# source_eagle.net
KiCad netlist of a schematic drawn in EAGLE
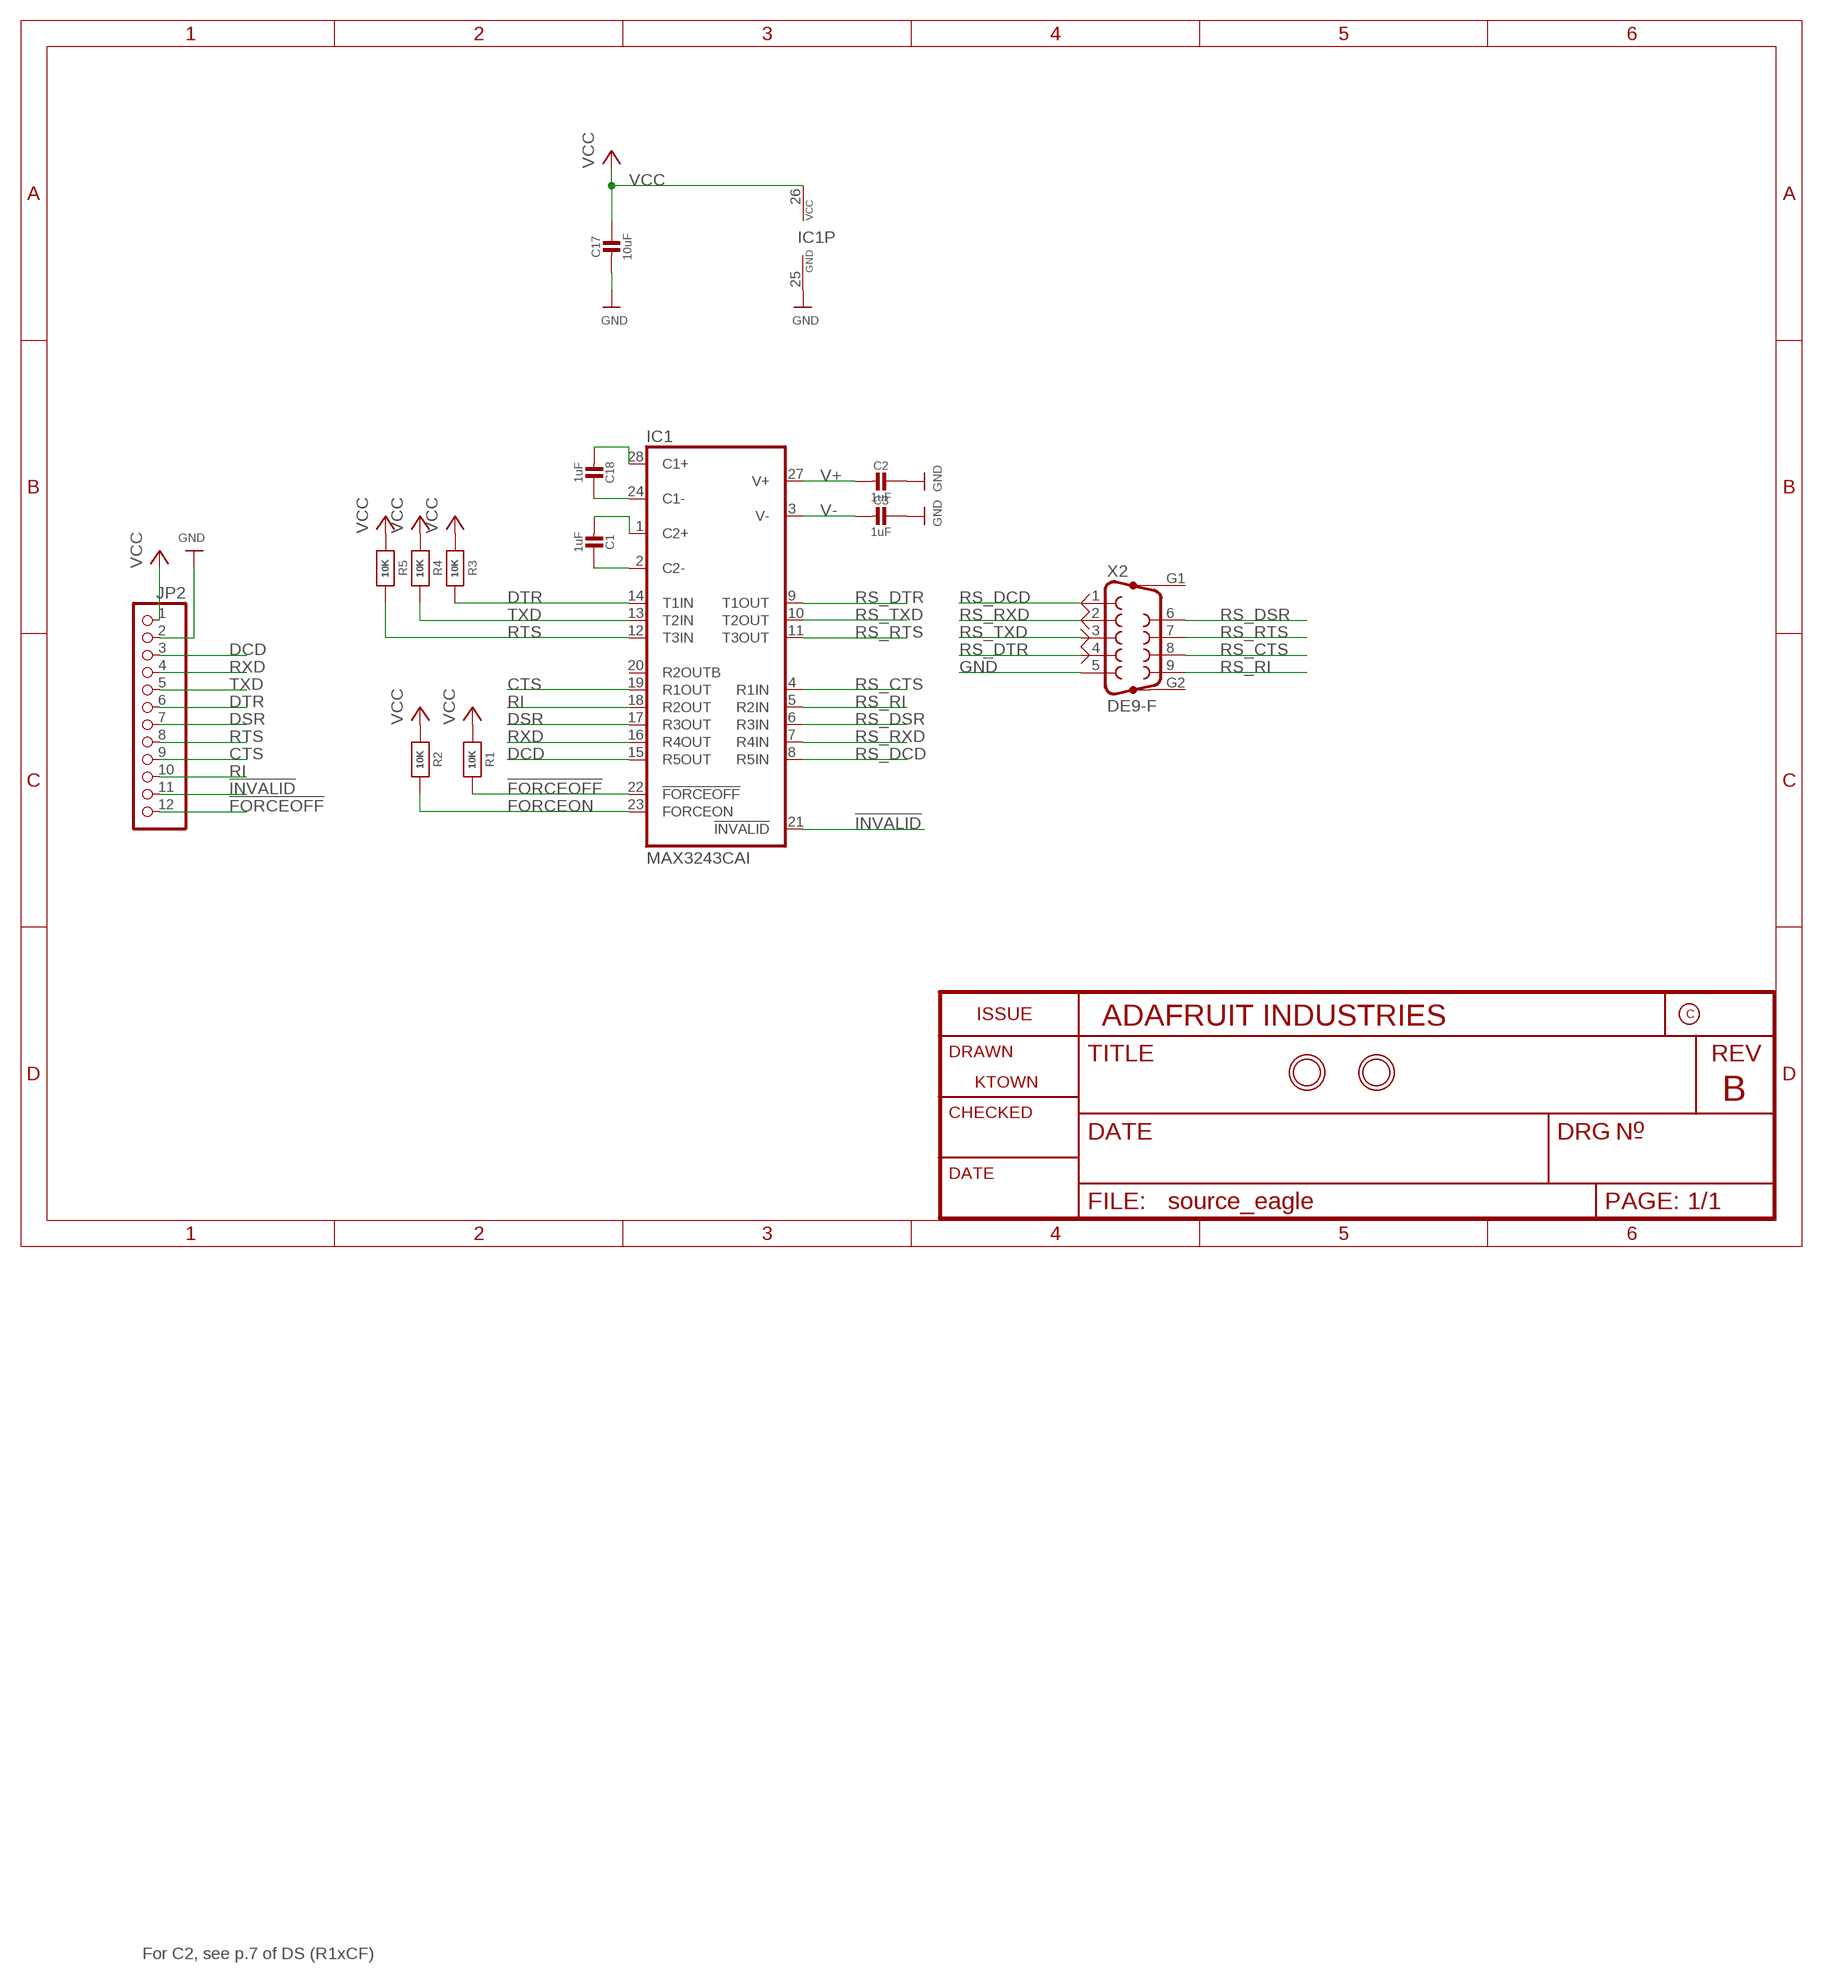
[diagram p0: schematic, sheet 1]

(export (version "E")
  (design (tool "Eeschema 10.0.6"))
  (components
    (comp (ref "C1")
      (value "1uF")
      (footprint "eagle-import:0603-NO")
      (libsource (lib "eagle-import") (part "CAP_CERAMIC0603_NO"))
    )
    (comp (ref "C2")
      (value "1uF")
      (footprint "eagle-import:0603-NO")
      (libsource (lib "eagle-import") (part "CAP_CERAMIC0603_NO"))
    )
    (comp (ref "C3")
      (value "1uF")
      (footprint "eagle-import:0603-NO")
      (libsource (lib "eagle-import") (part "CAP_CERAMIC0603_NO"))
    )
    (comp (ref "C17")
      (value "10uF")
      (footprint "eagle-import:0805-NO")
      (libsource (lib "eagle-import") (part "CAP_CERAMIC0805-NOOUTLINE"))
    )
    (comp (ref "C18")
      (value "1uF")
      (footprint "eagle-import:0603-NO")
      (libsource (lib "eagle-import") (part "CAP_CERAMIC0603_NO"))
    )
    (comp (ref "IC1")
      (value "MAX3243CAI")
      (footprint "eagle-import:SSOP28")
      (fields (field (name "MF") "MAXIM") (field (name "MPN") "MAX3243CAI+"))
      (libsource (lib "eagle-import") (part "MAX3243AIC"))
    )
    (comp (ref "JP2")
      (value "HEADER-1X1276MIL")
      (footprint "eagle-import:1X12_ROUND_76MIL")
      (libsource (lib "eagle-import") (part "HEADER-1X1276MIL"))
    )
    (comp (ref "R1")
      (value "10K")
      (footprint "eagle-import:0603-NO")
      (libsource (lib "eagle-import") (part "RESISTOR_0603_NOOUT"))
    )
    (comp (ref "R2")
      (value "10K")
      (footprint "eagle-import:0603-NO")
      (libsource (lib "eagle-import") (part "RESISTOR_0603_NOOUT"))
    )
    (comp (ref "R3")
      (value "10K")
      (footprint "eagle-import:0603-NO")
      (libsource (lib "eagle-import") (part "RESISTOR_0603_NOOUT"))
    )
    (comp (ref "R4")
      (value "10K")
      (footprint "eagle-import:0603-NO")
      (libsource (lib "eagle-import") (part "RESISTOR_0603_NOOUT"))
    )
    (comp (ref "R5")
      (value "10K")
      (footprint "eagle-import:0603-NO")
      (libsource (lib "eagle-import") (part "RESISTOR_0603_NOOUT"))
    )
    (comp (ref "U$2")
      (value "MOUNTINGHOLE3.0THIN")
      (footprint "eagle-import:MOUNTINGHOLE_3.0_PLATEDTHIN")
      (libsource (lib "eagle-import") (part "MOUNTINGHOLE3.0THIN"))
    )
    (comp (ref "U$3")
      (value "MOUNTINGHOLE3.0THIN")
      (footprint "eagle-import:MOUNTINGHOLE_3.0_PLATEDTHIN")
      (libsource (lib "eagle-import") (part "MOUNTINGHOLE3.0THIN"))
    )
    (comp (ref "X2")
      (value "DE9-F")
      (footprint "eagle-import:F09HP")
      (libsource (lib "eagle-import") (part "F09HP"))
    )
  )
  (nets
    (net (code "1") (name "/CTS") (class "Default")
      (node (ref "IC1") (pin "19") (pinfunction "R1OUT_19") (pintype "output"))
      (node (ref "JP2") (pin "9") (pinfunction "9_9") (pintype "passive"))
    )
    (net (code "2") (name "/DCD") (class "Default")
      (node (ref "IC1") (pin "15") (pinfunction "R5OUT_15") (pintype "output"))
      (node (ref "JP2") (pin "3") (pinfunction "3_3") (pintype "passive"))
    )
    (net (code "3") (name "/DSR") (class "Default")
      (node (ref "IC1") (pin "17") (pinfunction "R3OUT_17") (pintype "output"))
      (node (ref "JP2") (pin "7") (pinfunction "7_7") (pintype "passive"))
    )
    (net (code "4") (name "/DTR") (class "Default")
      (node (ref "IC1") (pin "14") (pinfunction "T1IN_14") (pintype "input"))
      (node (ref "JP2") (pin "6") (pinfunction "6_6") (pintype "passive"))
      (node (ref "R3") (pin "2") (pinfunction "2_2") (pintype "passive"))
    )
    (net (code "5") (name "/FORCEON") (class "Default")
      (node (ref "IC1") (pin "23") (pinfunction "FORCEON_23") (pintype "input"))
      (node (ref "R2") (pin "2") (pinfunction "2_2") (pintype "passive"))
    )
    (net (code "6") (name "/RI") (class "Default")
      (node (ref "IC1") (pin "18") (pinfunction "R2OUT_18") (pintype "output"))
      (node (ref "JP2") (pin "10") (pinfunction "10_10") (pintype "passive"))
    )
    (net (code "7") (name "/RS_CTS") (class "Default")
      (node (ref "IC1") (pin "4") (pinfunction "R1IN_4") (pintype "input"))
      (node (ref "X2") (pin "8") (pinfunction "8_8") (pintype "passive"))
    )
    (net (code "8") (name "/RS_DCD") (class "Default")
      (node (ref "IC1") (pin "8") (pinfunction "R5IN_8") (pintype "input"))
      (node (ref "X2") (pin "1") (pinfunction "1_1") (pintype "passive"))
    )
    (net (code "9") (name "/RS_DSR") (class "Default")
      (node (ref "IC1") (pin "6") (pinfunction "R3IN_6") (pintype "input"))
      (node (ref "X2") (pin "6") (pinfunction "6_6") (pintype "passive"))
    )
    (net (code "10") (name "/RS_DTR") (class "Default")
      (node (ref "IC1") (pin "9") (pinfunction "T1OUT_9") (pintype "output"))
      (node (ref "X2") (pin "4") (pinfunction "4_4") (pintype "passive"))
    )
    (net (code "11") (name "/RS_RI") (class "Default")
      (node (ref "IC1") (pin "5") (pinfunction "R2IN_5") (pintype "input"))
      (node (ref "X2") (pin "9") (pinfunction "9_9") (pintype "passive"))
    )
    (net (code "12") (name "/RS_RTS") (class "Default")
      (node (ref "IC1") (pin "11") (pinfunction "T3OUT_11") (pintype "output"))
      (node (ref "X2") (pin "7") (pinfunction "7_7") (pintype "passive"))
    )
    (net (code "13") (name "/RS_RXD") (class "Default")
      (node (ref "IC1") (pin "7") (pinfunction "R4IN_7") (pintype "input"))
      (node (ref "X2") (pin "2") (pinfunction "2_2") (pintype "passive"))
    )
    (net (code "14") (name "/RS_TXD") (class "Default")
      (node (ref "IC1") (pin "10") (pinfunction "T2OUT_10") (pintype "output"))
      (node (ref "X2") (pin "3") (pinfunction "3_3") (pintype "passive"))
    )
    (net (code "15") (name "/RTS") (class "Default")
      (node (ref "IC1") (pin "12") (pinfunction "T3IN_12") (pintype "input"))
      (node (ref "JP2") (pin "8") (pinfunction "8_8") (pintype "passive"))
      (node (ref "R5") (pin "2") (pinfunction "2_2") (pintype "passive"))
    )
    (net (code "16") (name "/RXD") (class "Default")
      (node (ref "IC1") (pin "16") (pinfunction "R4OUT_16") (pintype "output"))
      (node (ref "JP2") (pin "4") (pinfunction "4_4") (pintype "passive"))
    )
    (net (code "17") (name "/TXD") (class "Default")
      (node (ref "IC1") (pin "13") (pinfunction "T2IN_13") (pintype "input"))
      (node (ref "JP2") (pin "5") (pinfunction "5_5") (pintype "passive"))
      (node (ref "R4") (pin "2") (pinfunction "2_2") (pintype "passive"))
    )
    (net (code "18") (name "/V+") (class "Default")
      (node (ref "C2") (pin "2") (pinfunction "2_2") (pintype "passive"))
      (node (ref "IC1") (pin "27") (pinfunction "V+_27") (pintype "passive"))
    )
    (net (code "19") (name "/V-") (class "Default")
      (node (ref "C3") (pin "2") (pinfunction "2_2") (pintype "passive"))
      (node (ref "IC1") (pin "3") (pinfunction "V-_3") (pintype "passive"))
    )
    (net (code "20") (name "/~{FORCEOFF}") (class "Default")
      (node (ref "IC1") (pin "22") (pinfunction "~{FORCEOFF}_22") (pintype "input"))
      (node (ref "JP2") (pin "12") (pinfunction "12_12") (pintype "passive"))
      (node (ref "R1") (pin "2") (pinfunction "2_2") (pintype "passive"))
    )
    (net (code "21") (name "/~{INVALID}") (class "Default")
      (node (ref "IC1") (pin "21") (pinfunction "~{INVALID}_21") (pintype "input"))
      (node (ref "JP2") (pin "11") (pinfunction "11_11") (pintype "passive"))
    )
    (net (code "22") (name "GND") (class "Default")
      (node (ref "C17") (pin "2") (pinfunction "2_2") (pintype "passive"))
      (node (ref "C2") (pin "1") (pinfunction "1_1") (pintype "passive"))
      (node (ref "C3") (pin "1") (pinfunction "1_1") (pintype "passive"))
      (node (ref "IC1") (pin "25") (pinfunction "GND_25") (pintype "power_in"))
      (node (ref "JP2") (pin "2") (pinfunction "2_2") (pintype "passive"))
      (node (ref "X2") (pin "5") (pinfunction "5_5") (pintype "passive"))
    )
    (net (code "23") (name "Net-(IC1A-C1+)") (class "Default")
      (node (ref "C18") (pin "2") (pinfunction "2_2") (pintype "passive"))
      (node (ref "IC1") (pin "28") (pinfunction "C1+_28") (pintype "passive"))
    )
    (net (code "24") (name "Net-(IC1A-C1-)") (class "Default")
      (node (ref "C18") (pin "1") (pinfunction "1_1") (pintype "passive"))
      (node (ref "IC1") (pin "24") (pinfunction "C1-_24") (pintype "passive"))
    )
    (net (code "25") (name "Net-(IC1A-C2+)") (class "Default")
      (node (ref "C1") (pin "2") (pinfunction "2_2") (pintype "passive"))
      (node (ref "IC1") (pin "1") (pinfunction "C2+_1") (pintype "passive"))
    )
    (net (code "26") (name "Net-(IC1A-C2-)") (class "Default")
      (node (ref "C1") (pin "1") (pinfunction "1_1") (pintype "passive"))
      (node (ref "IC1") (pin "2") (pinfunction "C2-_2") (pintype "passive"))
    )
    (net (code "27") (name "VCC") (class "Default")
      (node (ref "C17") (pin "1") (pinfunction "1_1") (pintype "passive"))
      (node (ref "IC1") (pin "26") (pinfunction "VCC_26") (pintype "power_in"))
      (node (ref "JP2") (pin "1") (pinfunction "1_1") (pintype "passive"))
      (node (ref "R1") (pin "1") (pinfunction "1_1") (pintype "passive"))
      (node (ref "R2") (pin "1") (pinfunction "1_1") (pintype "passive"))
      (node (ref "R3") (pin "1") (pinfunction "1_1") (pintype "passive"))
      (node (ref "R4") (pin "1") (pinfunction "1_1") (pintype "passive"))
      (node (ref "R5") (pin "1") (pinfunction "1_1") (pintype "passive"))
    )
    (net (code "28") (name "unconnected-(IC1A-R2OUTB-Pad20)") (class "Default")
      (node (ref "IC1") (pin "20") (pinfunction "R2OUTB_20") (pintype "output"))
    )
    (net (code "29") (name "unconnected-(X2-PadG1)") (class "Default")
      (node (ref "X2") (pin "G1") (pinfunction "G1_G1") (pintype "passive"))
    )
    (net (code "30") (name "unconnected-(X2-PadG2)") (class "Default")
      (node (ref "X2") (pin "G2") (pinfunction "G2_G2") (pintype "passive"))
    )
  )
)
